# RoverMeter.net
KiCad netlist of a schematic drawn in EAGLE
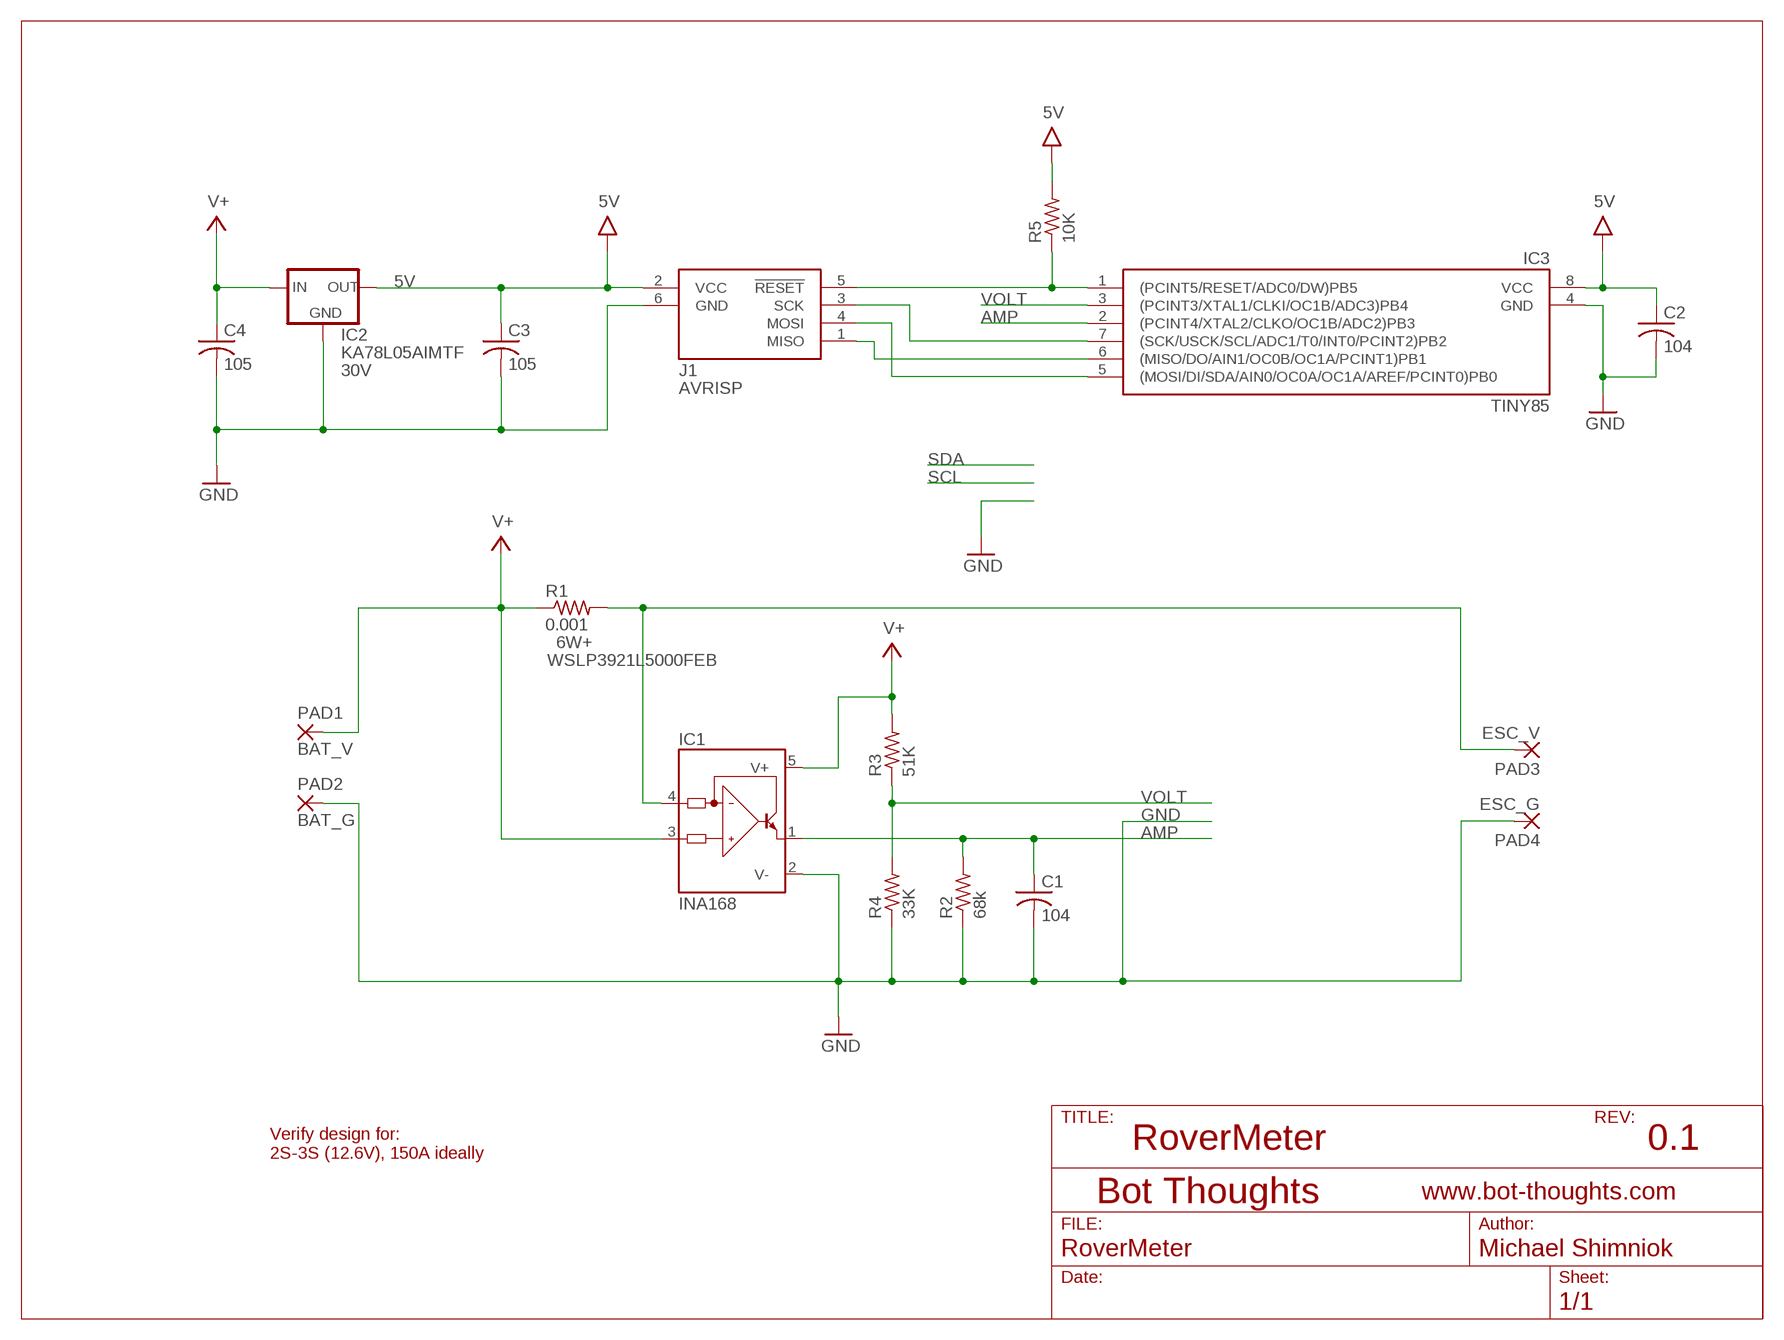
[diagram p0: schematic, sheet 1]

(export (version "E")
  (design (tool "Eeschema 10.0.6"))
  (components
    (comp (ref "C1")
      (value "104")
      (footprint "eagle-import:C0603")
      (libsource (lib "eagle-import") (part "resistor_C-USC0603"))
    )
    (comp (ref "C2")
      (value "104")
      (footprint "eagle-import:C0603")
      (libsource (lib "eagle-import") (part "C-USC0603"))
    )
    (comp (ref "C3")
      (value "105")
      (footprint "eagle-import:C0603")
      (libsource (lib "eagle-import") (part "C-USC0603"))
    )
    (comp (ref "C4")
      (value "105")
      (footprint "eagle-import:C0603")
      (libsource (lib "eagle-import") (part "C-USC0603"))
    )
    (comp (ref "IC1")
      (value "INA168")
      (footprint "eagle-import:SOT23-5")
      (fields (field (name "MF") "TEXAS INSTRUMENTS") (field (name "MPN") "INA168NA/250"))
      (libsource (lib "eagle-import") (part "INA168"))
    )
    (comp (ref "IC2")
      (value "KA78L05AIMTF")
      (footprint "eagle-import:SOT89")
      (fields (field (name "VOLTAGE") "30V"))
      (libsource (lib "eagle-import") (part "78LXX-SOT89"))
    )
    (comp (ref "IC3")
      (value "TINY85")
      (footprint "eagle-import:SOIC8")
      (libsource (lib "eagle-import") (part "TINY25/45/85-20SU"))
    )
    (comp (ref "J1")
      (value "AVRISP")
      (footprint "eagle-import:CON6P2R")
      (libsource (lib "eagle-import") (part "AVRISP6"))
    )
    (comp (ref "PAD1")
      (value "BAT_V")
      (footprint "eagle-import:3,81_1,4")
      (libsource (lib "eagle-import") (part "3,81/1,4"))
    )
    (comp (ref "PAD2")
      (value "BAT_G")
      (footprint "eagle-import:3,81_1,4")
      (libsource (lib "eagle-import") (part "3,81/1,4"))
    )
    (comp (ref "PAD3")
      (value "ESC_V")
      (footprint "eagle-import:3,81_1,4")
      (libsource (lib "eagle-import") (part "3,81/1,4"))
    )
    (comp (ref "PAD4")
      (value "ESC_G")
      (footprint "eagle-import:3,81_1,4")
      (libsource (lib "eagle-import") (part "3,81/1,4"))
    )
    (comp (ref "R1")
      (value "0.001")
      (footprint "eagle-import:WSLP3921")
      (fields (field (name "PARTNO") "WSLP3921L5000FEB") (field (name "POWER") "6W+"))
      (libsource (lib "eagle-import") (part "R-US_WSLP3921"))
    )
    (comp (ref "R2")
      (value "68k")
      (footprint "eagle-import:R0603")
      (libsource (lib "eagle-import") (part "R-US_R0603"))
    )
    (comp (ref "R3")
      (value "51K")
      (footprint "eagle-import:R0603")
      (libsource (lib "eagle-import") (part "resistor_R-US_R0603"))
    )
    (comp (ref "R4")
      (value "33K")
      (footprint "eagle-import:R0603")
      (libsource (lib "eagle-import") (part "resistor_R-US_R0603"))
    )
    (comp (ref "R5")
      (value "10K")
      (footprint "eagle-import:R0603")
      (libsource (lib "eagle-import") (part "resistor_R-US_R0603"))
    )
  )
  (nets
    (net (code "1") (name "/AMP") (class "Default")
      (node (ref "C1") (pin "1") (pinfunction "1_1") (pintype "passive"))
      (node (ref "IC1") (pin "1") (pinfunction "OUT_1") (pintype "output"))
      (node (ref "IC3") (pin "2") (pinfunction "(PCINT4/XTAL2/CLKO/OC1B/ADC2)PB3_2") (pintype "bidirectional"))
      (node (ref "R2") (pin "2") (pinfunction "2_2") (pintype "passive"))
    )
    (net (code "2") (name "/SCL") (class "Default")
      (node (ref "IC3") (pin "7") (pinfunction "(SCK/USCK/SCL/ADC1/T0/INT0/PCINT2)PB2_7") (pintype "bidirectional"))
      (node (ref "J1") (pin "3") (pinfunction "SCK_3") (pintype "output"))
    )
    (net (code "3") (name "/SDA") (class "Default")
      (node (ref "IC3") (pin "5") (pinfunction "(MOSI/DI/SDA/AIN0/OC0A/OC1A/AREF/PCINT0)PB0_5") (pintype "bidirectional"))
      (node (ref "J1") (pin "4") (pinfunction "MOSI_4") (pintype "output"))
    )
    (net (code "4") (name "/VOLT") (class "Default")
      (node (ref "IC3") (pin "3") (pinfunction "(PCINT3/XTAL1/CLKI/OC1B/ADC3)PB4_3") (pintype "bidirectional"))
      (node (ref "R3") (pin "1") (pinfunction "1_1") (pintype "passive"))
      (node (ref "R4") (pin "2") (pinfunction "2_2") (pintype "passive"))
    )
    (net (code "5") (name "5V") (class "Default")
      (node (ref "C2") (pin "1") (pinfunction "1_1") (pintype "passive"))
      (node (ref "C3") (pin "1") (pinfunction "1_1") (pintype "passive"))
      (node (ref "IC2") (pin "1") (pinfunction "OUT_1") (pintype "passive"))
      (node (ref "IC3") (pin "8") (pinfunction "VCC_8") (pintype "power_in"))
      (node (ref "J1") (pin "2") (pinfunction "VCC_2") (pintype "power_in"))
      (node (ref "R5") (pin "2") (pinfunction "2_2") (pintype "passive"))
    )
    (net (code "6") (name "GND") (class "Default")
      (node (ref "C1") (pin "2") (pinfunction "2_2") (pintype "passive"))
      (node (ref "C2") (pin "2") (pinfunction "2_2") (pintype "passive"))
      (node (ref "C3") (pin "2") (pinfunction "2_2") (pintype "passive"))
      (node (ref "C4") (pin "2") (pinfunction "2_2") (pintype "passive"))
      (node (ref "IC1") (pin "2") (pinfunction "V-_2") (pintype "power_in"))
      (node (ref "IC2") (pin "2") (pinfunction "GND_2") (pintype "input"))
      (node (ref "IC3") (pin "4") (pinfunction "GND_4") (pintype "power_in"))
      (node (ref "J1") (pin "6") (pinfunction "GND_6") (pintype "power_in"))
      (node (ref "PAD2") (pin "1") (pinfunction "P_1") (pintype "passive"))
      (node (ref "PAD4") (pin "1") (pinfunction "P_1") (pintype "passive"))
      (node (ref "R2") (pin "1") (pinfunction "1_1") (pintype "passive"))
      (node (ref "R4") (pin "1") (pinfunction "1_1") (pintype "passive"))
    )
    (net (code "7") (name "Net-(IC1-IN-)") (class "Default")
      (node (ref "IC1") (pin "4") (pinfunction "IN-_4") (pintype "input"))
      (node (ref "PAD3") (pin "1") (pinfunction "P_1") (pintype "passive"))
      (node (ref "R1") (pin "P$2") (pinfunction "2_P$2") (pintype "passive"))
    )
    (net (code "8") (name "Net-(IC3-(MISO{slash}DO{slash}AIN1{slash}OC0B{slash}OC1A{slash}PCINT1)PB1)") (class "Default")
      (node (ref "IC3") (pin "6") (pinfunction "(MISO/DO/AIN1/OC0B/OC1A/PCINT1)PB1_6") (pintype "bidirectional"))
      (node (ref "J1") (pin "1") (pinfunction "MISO_1") (pintype "input"))
    )
    (net (code "9") (name "Net-(IC3-(PCINT5{slash}RESET{slash}ADC0{slash}DW)PB5)") (class "Default")
      (node (ref "IC3") (pin "1") (pinfunction "(PCINT5/RESET/ADC0/DW)PB5_1") (pintype "bidirectional"))
      (node (ref "J1") (pin "5") (pinfunction "~{RESET}_5") (pintype "output"))
      (node (ref "R5") (pin "1") (pinfunction "1_1") (pintype "passive"))
    )
    (net (code "10") (name "V+") (class "Default")
      (node (ref "C4") (pin "1") (pinfunction "1_1") (pintype "passive"))
      (node (ref "IC1") (pin "3") (pinfunction "IN+_3") (pintype "input"))
      (node (ref "IC1") (pin "5") (pinfunction "V+_5") (pintype "power_in"))
      (node (ref "IC2") (pin "3") (pinfunction "IN_3") (pintype "input"))
      (node (ref "PAD1") (pin "1") (pinfunction "P_1") (pintype "passive"))
      (node (ref "R1") (pin "P$1") (pinfunction "1_P$1") (pintype "passive"))
      (node (ref "R3") (pin "2") (pinfunction "2_2") (pintype "passive"))
    )
  )
)
